# 2021_PWR_REVD.net
KiCad netlist of a schematic drawn in EAGLE
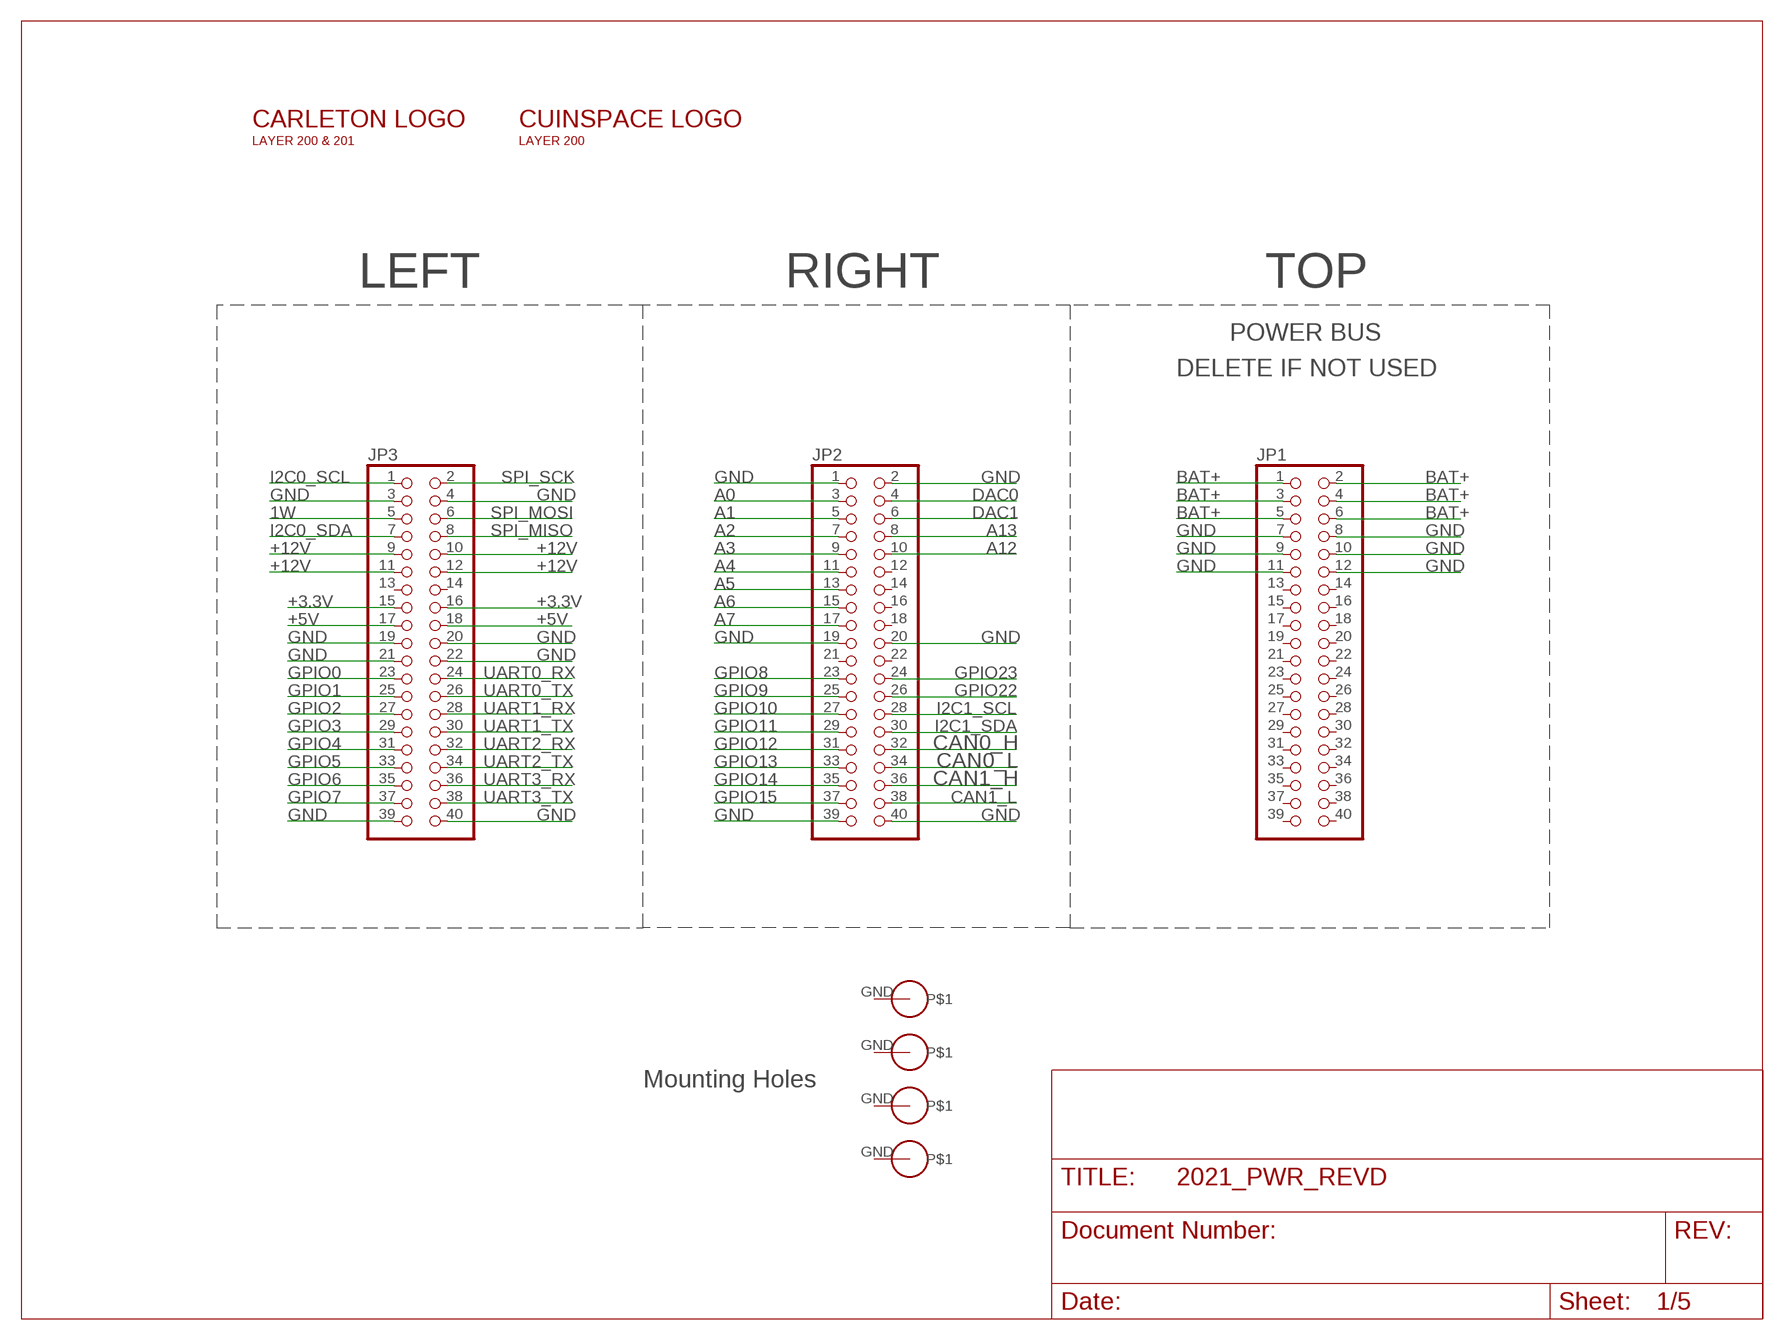
[diagram p0: schematic, sheet 1]
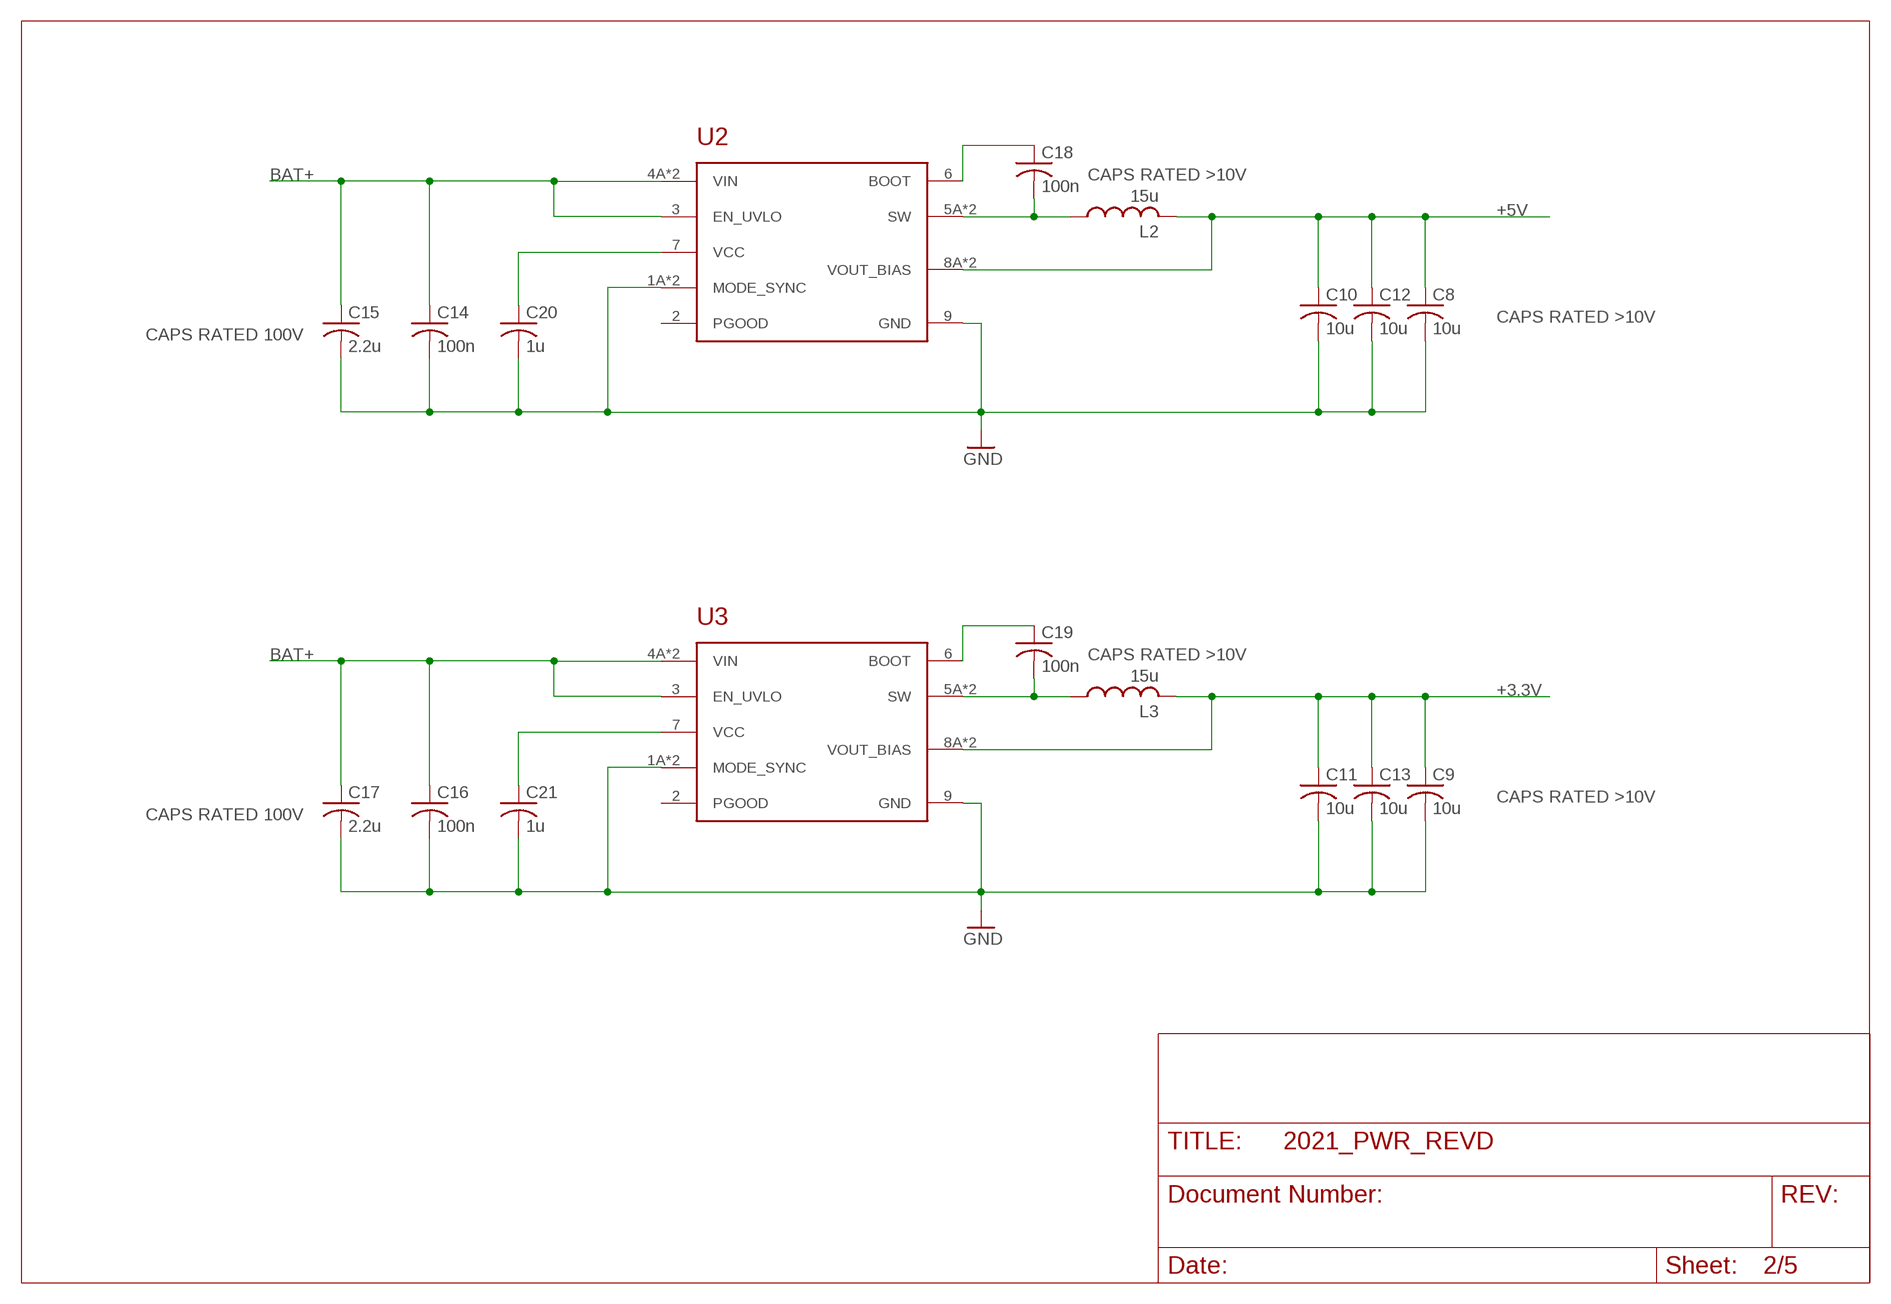
[diagram p1: schematic, sheet 2]
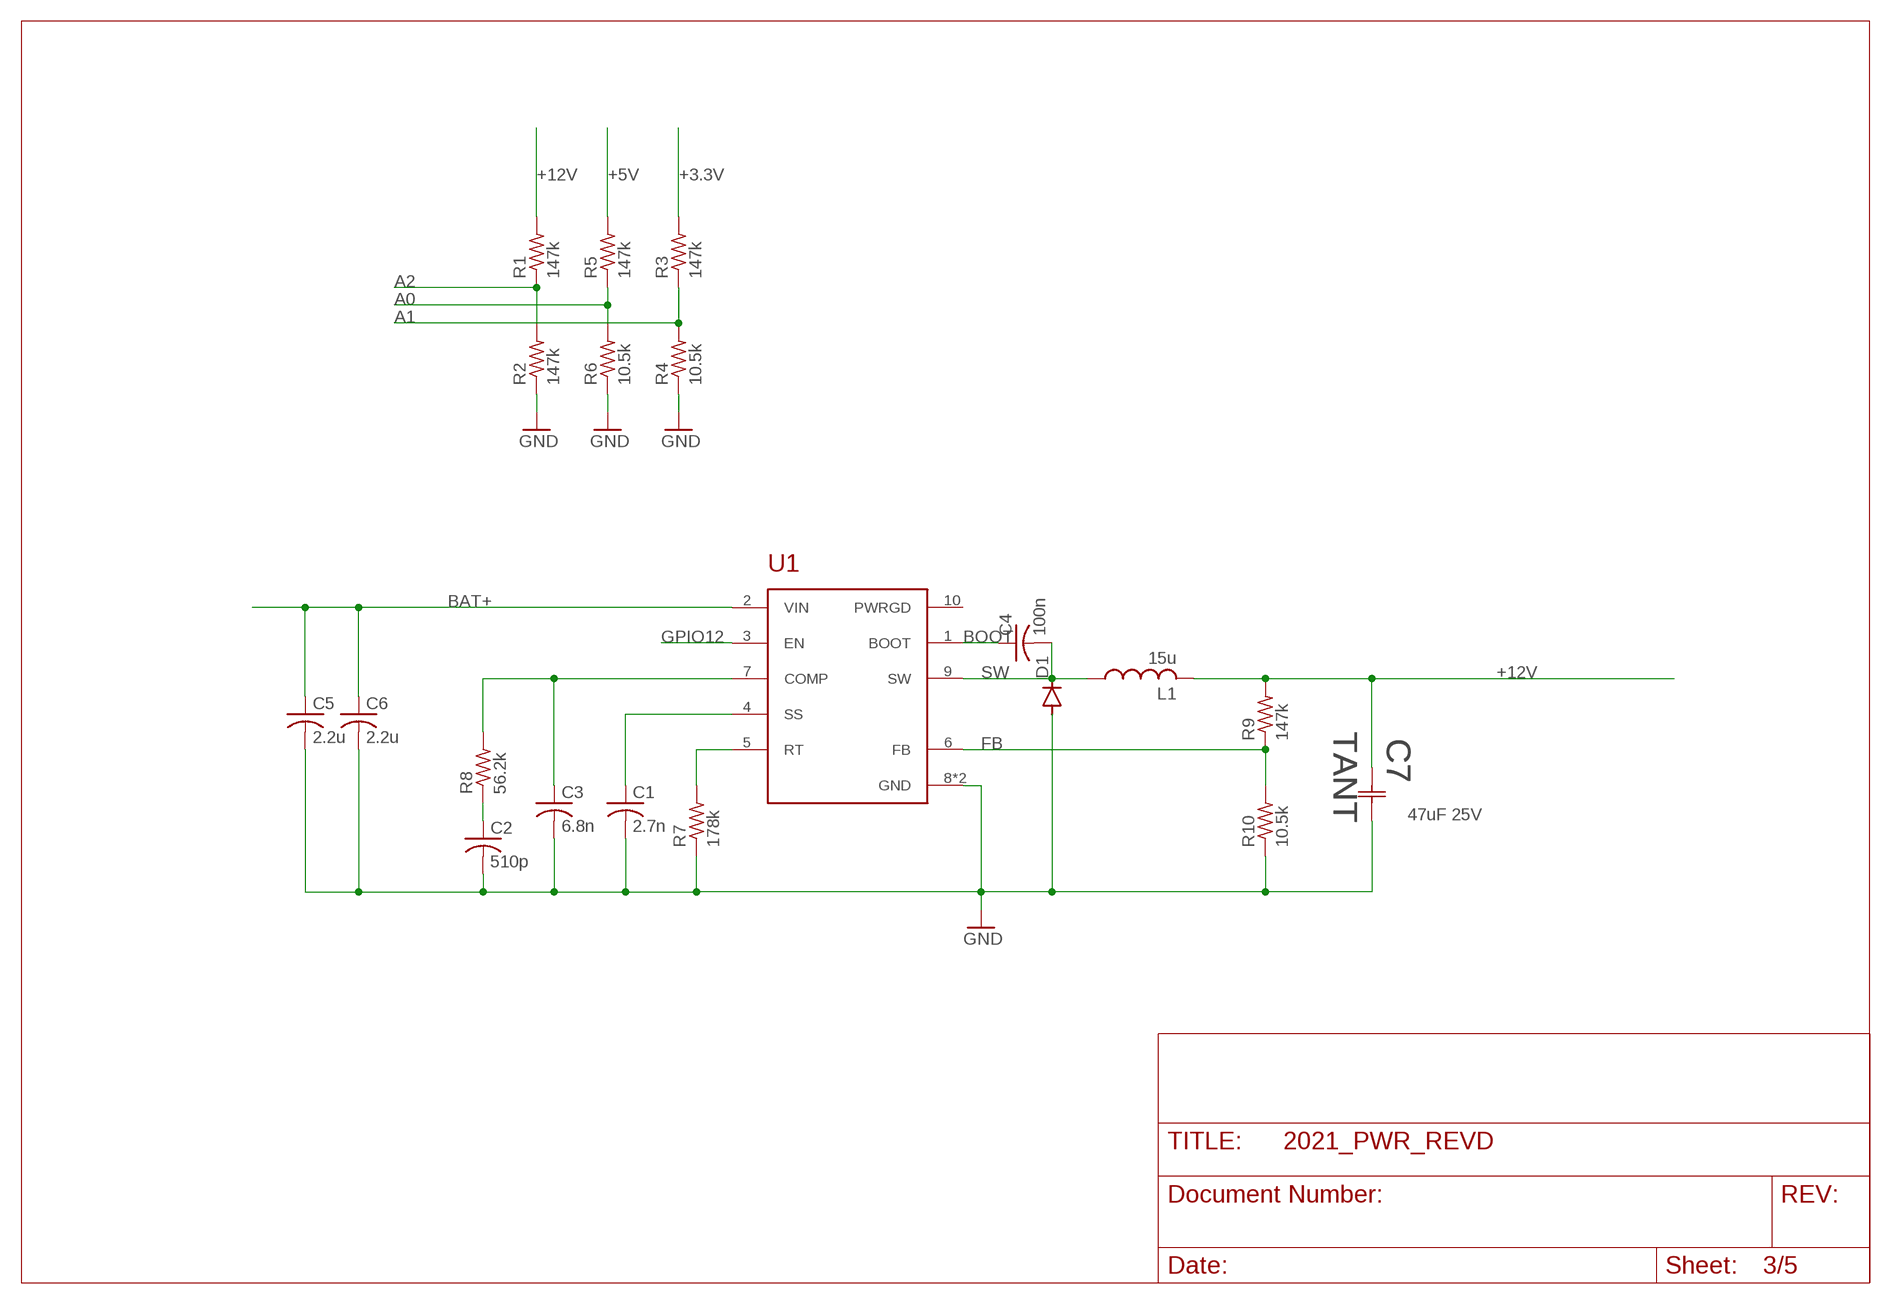
[diagram p2: schematic, sheet 3]

(export (version "E")
  (design (tool "Eeschema 10.0.6"))
  (components
    (comp (ref "C1")
      (value "2.7n")
      (footprint "eagle-import:C0805")
      (libsource (lib "eagle-import") (part "C-USC0805"))
    )
    (comp (ref "C2")
      (value "510p")
      (footprint "eagle-import:C0805")
      (libsource (lib "eagle-import") (part "C-USC0805"))
    )
    (comp (ref "C3")
      (value "6.8n")
      (footprint "eagle-import:C0805")
      (libsource (lib "eagle-import") (part "C-USC0805"))
    )
    (comp (ref "C4")
      (value "100n")
      (footprint "eagle-import:C0805")
      (libsource (lib "eagle-import") (part "C-USC0805"))
    )
    (comp (ref "C5")
      (value "2.2u")
      (footprint "eagle-import:C0805")
      (libsource (lib "eagle-import") (part "C-USC0805"))
    )
    (comp (ref "C6")
      (value "2.2u")
      (footprint "eagle-import:C0805")
      (libsource (lib "eagle-import") (part "C-USC0805"))
    )
    (comp (ref "C7")
      (value "TANT")
      (footprint "eagle-import:TAJD")
      (fields (field (name "MANUFACTURER_PART_NUMBER") "TAJD226K016RNJ"))
      (libsource (lib "eagle-import") (part "TANT"))
    )
    (comp (ref "D1")
      (value "SCH_DIODE_10A_100VFSV10100V")
      (footprint "eagle-import:TO-277-3")
      (libsource (lib "eagle-import") (part "SCH_DIODE_10A_100VFSV10100V"))
    )
    (comp (ref "L1")
      (value "15u")
      (footprint "eagle-import:13.5X12.5")
      (libsource (lib "eagle-import") (part "IND_15UH_9A_28MOHMSRP1265A-150M"))
    )
    (comp (ref "R1")
      (value "147k")
      (footprint "eagle-import:R0805")
      (libsource (lib "eagle-import") (part "R-US_R0805"))
    )
    (comp (ref "R2")
      (value "147k")
      (footprint "eagle-import:R0805")
      (libsource (lib "eagle-import") (part "R-US_R0805"))
    )
    (comp (ref "R3")
      (value "147k")
      (footprint "eagle-import:R0805")
      (libsource (lib "eagle-import") (part "R-US_R0805"))
    )
    (comp (ref "R4")
      (value "10.5k")
      (footprint "eagle-import:R0805")
      (libsource (lib "eagle-import") (part "R-US_R0805"))
    )
    (comp (ref "R5")
      (value "147k")
      (footprint "eagle-import:R0805")
      (libsource (lib "eagle-import") (part "R-US_R0805"))
    )
    (comp (ref "R6")
      (value "10.5k")
      (footprint "eagle-import:R0805")
      (libsource (lib "eagle-import") (part "R-US_R0805"))
    )
    (comp (ref "R7")
      (value "178k")
      (footprint "eagle-import:R0805")
      (libsource (lib "eagle-import") (part "R-US_R0805"))
    )
    (comp (ref "R8")
      (value "56.2k")
      (footprint "eagle-import:R0805")
      (libsource (lib "eagle-import") (part "R-US_R0805"))
    )
    (comp (ref "R9")
      (value "147k")
      (footprint "eagle-import:R0805")
      (libsource (lib "eagle-import") (part "R-US_R0805"))
    )
    (comp (ref "R10")
      (value "10.5k")
      (footprint "eagle-import:R0805")
      (libsource (lib "eagle-import") (part "R-US_R0805"))
    )
    (comp (ref "U1")
      (value "TPS54561")
      (footprint "eagle-import:10-WSON")
      (libsource (lib "eagle-import") (part "TPS54561"))
    )
    (comp (ref "$$U$1")
      (value "PS/104-MOUNTING-HOLE")
      (footprint "eagle-import:PC_104-MOUNTING-HOLE")
      (libsource (lib "eagle-import") (part "PS/104-MOUNTING-HOLE"))
    )
    (comp (ref "JP1")
      (value "PINHD-2X20")
      (footprint "eagle-import:2X20")
      (libsource (lib "eagle-import") (part "PINHD-2X20"))
    )
    (comp (ref "JP2")
      (value "PINHD-2X20")
      (footprint "eagle-import:2X20")
      (libsource (lib "eagle-import") (part "PINHD-2X20"))
    )
    (comp (ref "JP3")
      (value "PINHD-2X20")
      (footprint "eagle-import:2X20")
      (libsource (lib "eagle-import") (part "PINHD-2X20"))
    )
    (comp (ref "U$1")
      (value "PS/104-MOUNTING-HOLE")
      (footprint "eagle-import:PC_104-MOUNTING-HOLE")
      (libsource (lib "eagle-import") (part "PS/104-MOUNTING-HOLE"))
    )
    (comp (ref "U$2")
      (value "PS/104-MOUNTING-HOLE")
      (footprint "eagle-import:PC_104-MOUNTING-HOLE")
      (libsource (lib "eagle-import") (part "PS/104-MOUNTING-HOLE"))
    )
    (comp (ref "U$3")
      (value "PS/104-MOUNTING-HOLE")
      (footprint "eagle-import:PC_104-MOUNTING-HOLE")
      (libsource (lib "eagle-import") (part "PS/104-MOUNTING-HOLE"))
    )
    (comp (ref "U$100")
      (value "INSPACE3CM_L")
      (footprint "eagle-import:INSPACE_3CM_LETTERS")
      (libsource (lib "eagle-import") (part "INSPACE3CM_L"))
    )
    (comp (ref "U$101")
      (value "CARLETON3CM")
      (footprint "eagle-import:CARLETONU_3CM")
      (libsource (lib "eagle-import") (part "CARLETON3CM"))
    )
    (comp (ref "C8")
      (value "10u")
      (footprint "eagle-import:C0805")
      (libsource (lib "eagle-import") (part "C-USC0805"))
    )
    (comp (ref "C9")
      (value "10u")
      (footprint "eagle-import:C0805")
      (libsource (lib "eagle-import") (part "C-USC0805"))
    )
    (comp (ref "C10")
      (value "10u")
      (footprint "eagle-import:C0805")
      (libsource (lib "eagle-import") (part "C-USC0805"))
    )
    (comp (ref "C11")
      (value "10u")
      (footprint "eagle-import:C0805")
      (libsource (lib "eagle-import") (part "C-USC0805"))
    )
    (comp (ref "C12")
      (value "10u")
      (footprint "eagle-import:C0805")
      (libsource (lib "eagle-import") (part "C-USC0805"))
    )
    (comp (ref "C13")
      (value "10u")
      (footprint "eagle-import:C0805")
      (libsource (lib "eagle-import") (part "C-USC0805"))
    )
    (comp (ref "C14")
      (value "100n")
      (footprint "eagle-import:C0805")
      (libsource (lib "eagle-import") (part "C-USC0805"))
    )
    (comp (ref "C15")
      (value "2.2u")
      (footprint "eagle-import:C0805")
      (libsource (lib "eagle-import") (part "C-USC0805"))
    )
    (comp (ref "C16")
      (value "100n")
      (footprint "eagle-import:C0805")
      (libsource (lib "eagle-import") (part "C-USC0805"))
    )
    (comp (ref "C17")
      (value "2.2u")
      (footprint "eagle-import:C0805")
      (libsource (lib "eagle-import") (part "C-USC0805"))
    )
    (comp (ref "C18")
      (value "100n")
      (footprint "eagle-import:C0805")
      (libsource (lib "eagle-import") (part "C-USC0805"))
    )
    (comp (ref "C19")
      (value "100n")
      (footprint "eagle-import:C0805")
      (libsource (lib "eagle-import") (part "C-USC0805"))
    )
    (comp (ref "C20")
      (value "1u")
      (footprint "eagle-import:C0805")
      (libsource (lib "eagle-import") (part "C-USC0805"))
    )
    (comp (ref "C21")
      (value "1u")
      (footprint "eagle-import:C0805")
      (libsource (lib "eagle-import") (part "C-USC0805"))
    )
    (comp (ref "L2")
      (value "15u")
      (footprint "eagle-import:13.5X12.5")
      (libsource (lib "eagle-import") (part "IND_15UH_9A_28MOHMSRP1265A-150M"))
    )
    (comp (ref "L3")
      (value "15u")
      (footprint "eagle-import:13.5X12.5")
      (libsource (lib "eagle-import") (part "IND_15UH_9A_28MOHMSRP1265A-150M"))
    )
    (comp (ref "U2")
      (value "LMR36506LMR36506MSC3")
      (footprint "eagle-import:9-VFQFN")
      (libsource (lib "eagle-import") (part "LMR36506LMR36506MSC3"))
    )
    (comp (ref "U3")
      (value "LMR36506LMR36506MSC3")
      (footprint "eagle-import:9-VFQFN")
      (libsource (lib "eagle-import") (part "LMR36506LMR36506MSC3"))
    )
  )
  (nets
    (net (code "1") (name "+3.3V") (class "Default")
      (node (ref "C11") (pin "1") (pinfunction "1_1") (pintype "passive"))
      (node (ref "C13") (pin "1") (pinfunction "1_1") (pintype "passive"))
      (node (ref "C9") (pin "1") (pinfunction "1_1") (pintype "passive"))
      (node (ref "JP3") (pin "15") (pinfunction "15_15") (pintype "passive"))
      (node (ref "JP3") (pin "16") (pinfunction "16_16") (pintype "passive"))
      (node (ref "L3") (pin "P$2") (pinfunction "2_P$2") (pintype "passive"))
      (node (ref "R3") (pin "2") (pinfunction "2_2") (pintype "passive"))
      (node (ref "U3") (pin "8A") (pinfunction "VOUT_BIAS_8A") (pintype "bidirectional"))
      (node (ref "U3") (pin "8B") (pinfunction "VOUT_BIAS_8B") (pintype "bidirectional"))
    )
    (net (code "2") (name "+5V") (class "Default")
      (node (ref "C10") (pin "1") (pinfunction "1_1") (pintype "passive"))
      (node (ref "C12") (pin "1") (pinfunction "1_1") (pintype "passive"))
      (node (ref "C8") (pin "1") (pinfunction "1_1") (pintype "passive"))
      (node (ref "JP3") (pin "17") (pinfunction "17_17") (pintype "passive"))
      (node (ref "JP3") (pin "18") (pinfunction "18_18") (pintype "passive"))
      (node (ref "L2") (pin "P$2") (pinfunction "2_P$2") (pintype "passive"))
      (node (ref "R5") (pin "2") (pinfunction "2_2") (pintype "passive"))
      (node (ref "U2") (pin "8A") (pinfunction "VOUT_BIAS_8A") (pintype "bidirectional"))
      (node (ref "U2") (pin "8B") (pinfunction "VOUT_BIAS_8B") (pintype "bidirectional"))
    )
    (net (code "3") (name "+12V") (class "Default")
      (node (ref "C7") (pin "1") (pinfunction "11_1") (pintype "passive"))
      (node (ref "JP3") (pin "10") (pinfunction "10_10") (pintype "passive"))
      (node (ref "JP3") (pin "11") (pinfunction "11_11") (pintype "passive"))
      (node (ref "JP3") (pin "12") (pinfunction "12_12") (pintype "passive"))
      (node (ref "JP3") (pin "9") (pinfunction "9_9") (pintype "passive"))
      (node (ref "L1") (pin "P$2") (pinfunction "2_P$2") (pintype "passive"))
      (node (ref "R1") (pin "2") (pinfunction "2_2") (pintype "passive"))
      (node (ref "R9") (pin "2") (pinfunction "2_2") (pintype "passive"))
    )
    (net (code "4") (name "1W") (class "Default")
      (node (ref "JP3") (pin "5") (pinfunction "5_5") (pintype "passive"))
    )
    (net (code "5") (name "A0") (class "Default")
      (node (ref "JP2") (pin "3") (pinfunction "3_3") (pintype "passive"))
      (node (ref "R5") (pin "1") (pinfunction "1_1") (pintype "passive"))
      (node (ref "R6") (pin "2") (pinfunction "2_2") (pintype "passive"))
    )
    (net (code "6") (name "A1") (class "Default")
      (node (ref "JP2") (pin "5") (pinfunction "5_5") (pintype "passive"))
      (node (ref "R3") (pin "1") (pinfunction "1_1") (pintype "passive"))
      (node (ref "R4") (pin "2") (pinfunction "2_2") (pintype "passive"))
    )
    (net (code "7") (name "A2") (class "Default")
      (node (ref "JP2") (pin "7") (pinfunction "7_7") (pintype "passive"))
      (node (ref "R1") (pin "1") (pinfunction "1_1") (pintype "passive"))
      (node (ref "R2") (pin "2") (pinfunction "2_2") (pintype "passive"))
    )
    (net (code "8") (name "A3") (class "Default")
      (node (ref "JP2") (pin "9") (pinfunction "9_9") (pintype "passive"))
    )
    (net (code "9") (name "A4") (class "Default")
      (node (ref "JP2") (pin "11") (pinfunction "11_11") (pintype "passive"))
    )
    (net (code "10") (name "A5") (class "Default")
      (node (ref "JP2") (pin "13") (pinfunction "13_13") (pintype "passive"))
    )
    (net (code "11") (name "A6") (class "Default")
      (node (ref "JP2") (pin "15") (pinfunction "15_15") (pintype "passive"))
    )
    (net (code "12") (name "A7") (class "Default")
      (node (ref "JP2") (pin "17") (pinfunction "17_17") (pintype "passive"))
    )
    (net (code "13") (name "A12") (class "Default")
      (node (ref "JP2") (pin "10") (pinfunction "10_10") (pintype "passive"))
    )
    (net (code "14") (name "A13") (class "Default")
      (node (ref "JP2") (pin "8") (pinfunction "8_8") (pintype "passive"))
    )
    (net (code "15") (name "BAT+") (class "Default")
      (node (ref "C14") (pin "1") (pinfunction "1_1") (pintype "passive"))
      (node (ref "C15") (pin "1") (pinfunction "1_1") (pintype "passive"))
      (node (ref "C16") (pin "1") (pinfunction "1_1") (pintype "passive"))
      (node (ref "C17") (pin "1") (pinfunction "1_1") (pintype "passive"))
      (node (ref "C5") (pin "1") (pinfunction "1_1") (pintype "passive"))
      (node (ref "C6") (pin "1") (pinfunction "1_1") (pintype "passive"))
      (node (ref "JP1") (pin "1") (pinfunction "1_1") (pintype "passive"))
      (node (ref "JP1") (pin "2") (pinfunction "2_2") (pintype "passive"))
      (node (ref "JP1") (pin "3") (pinfunction "3_3") (pintype "passive"))
      (node (ref "JP1") (pin "4") (pinfunction "4_4") (pintype "passive"))
      (node (ref "JP1") (pin "5") (pinfunction "5_5") (pintype "passive"))
      (node (ref "JP1") (pin "6") (pinfunction "6_6") (pintype "passive"))
      (node (ref "U1") (pin "2") (pinfunction "VIN_2") (pintype "bidirectional"))
      (node (ref "U2") (pin "3") (pinfunction "EN_UVLO_3") (pintype "bidirectional"))
      (node (ref "U2") (pin "4A") (pinfunction "VIN_4A") (pintype "bidirectional"))
      (node (ref "U2") (pin "4B") (pinfunction "VIN_4B") (pintype "bidirectional"))
      (node (ref "U3") (pin "3") (pinfunction "EN_UVLO_3") (pintype "bidirectional"))
      (node (ref "U3") (pin "4A") (pinfunction "VIN_4A") (pintype "bidirectional"))
      (node (ref "U3") (pin "4B") (pinfunction "VIN_4B") (pintype "bidirectional"))
    )
    (net (code "16") (name "BOOT") (class "Default")
      (node (ref "C4") (pin "1") (pinfunction "1_1") (pintype "passive"))
      (node (ref "U1") (pin "1") (pinfunction "BOOT_1") (pintype "bidirectional"))
    )
    (net (code "17") (name "CAN0_H") (class "Default")
      (node (ref "JP2") (pin "32") (pinfunction "32_32") (pintype "passive"))
    )
    (net (code "18") (name "CAN0_L") (class "Default")
      (node (ref "JP2") (pin "34") (pinfunction "34_34") (pintype "passive"))
    )
    (net (code "19") (name "CAN1_H") (class "Default")
      (node (ref "JP2") (pin "36") (pinfunction "36_36") (pintype "passive"))
    )
    (net (code "20") (name "CAN1_L") (class "Default")
      (node (ref "JP2") (pin "38") (pinfunction "38_38") (pintype "passive"))
    )
    (net (code "21") (name "DAC0") (class "Default")
      (node (ref "JP2") (pin "4") (pinfunction "4_4") (pintype "passive"))
    )
    (net (code "22") (name "DAC1") (class "Default")
      (node (ref "JP2") (pin "6") (pinfunction "6_6") (pintype "passive"))
    )
    (net (code "23") (name "FB") (class "Default")
      (node (ref "R10") (pin "2") (pinfunction "2_2") (pintype "passive"))
      (node (ref "R9") (pin "1") (pinfunction "1_1") (pintype "passive"))
      (node (ref "U1") (pin "6") (pinfunction "FB_6") (pintype "bidirectional"))
    )
    (net (code "24") (name "GND") (class "Default")
      (node (ref "C1") (pin "2") (pinfunction "2_2") (pintype "passive"))
      (node (ref "C10") (pin "2") (pinfunction "2_2") (pintype "passive"))
      (node (ref "C11") (pin "2") (pinfunction "2_2") (pintype "passive"))
      (node (ref "C12") (pin "2") (pinfunction "2_2") (pintype "passive"))
      (node (ref "C13") (pin "2") (pinfunction "2_2") (pintype "passive"))
      (node (ref "C14") (pin "2") (pinfunction "2_2") (pintype "passive"))
      (node (ref "C15") (pin "2") (pinfunction "2_2") (pintype "passive"))
      (node (ref "C16") (pin "2") (pinfunction "2_2") (pintype "passive"))
      (node (ref "C17") (pin "2") (pinfunction "2_2") (pintype "passive"))
      (node (ref "C2") (pin "2") (pinfunction "2_2") (pintype "passive"))
      (node (ref "C20") (pin "2") (pinfunction "2_2") (pintype "passive"))
      (node (ref "C21") (pin "2") (pinfunction "2_2") (pintype "passive"))
      (node (ref "C3") (pin "2") (pinfunction "2_2") (pintype "passive"))
      (node (ref "C5") (pin "2") (pinfunction "2_2") (pintype "passive"))
      (node (ref "C6") (pin "2") (pinfunction "2_2") (pintype "passive"))
      (node (ref "C7") (pin "2") (pinfunction "22_2") (pintype "passive"))
      (node (ref "C8") (pin "2") (pinfunction "2_2") (pintype "passive"))
      (node (ref "C9") (pin "2") (pinfunction "2_2") (pintype "passive"))
      (node (ref "D1") (pin "P$2") (pinfunction "A_P$2") (pintype "passive"))
      (node (ref "D1") (pin "P$3") (pinfunction "A_P$3") (pintype "passive"))
      (node (ref "JP1") (pin "10") (pinfunction "10_10") (pintype "passive"))
      (node (ref "JP1") (pin "11") (pinfunction "11_11") (pintype "passive"))
      (node (ref "JP1") (pin "12") (pinfunction "12_12") (pintype "passive"))
      (node (ref "JP1") (pin "7") (pinfunction "7_7") (pintype "passive"))
      (node (ref "JP1") (pin "8") (pinfunction "8_8") (pintype "passive"))
      (node (ref "JP1") (pin "9") (pinfunction "9_9") (pintype "passive"))
      (node (ref "JP2") (pin "1") (pinfunction "1_1") (pintype "passive"))
      (node (ref "JP2") (pin "19") (pinfunction "19_19") (pintype "passive"))
      (node (ref "JP2") (pin "2") (pinfunction "2_2") (pintype "passive"))
      (node (ref "JP2") (pin "20") (pinfunction "20_20") (pintype "passive"))
      (node (ref "JP2") (pin "39") (pinfunction "39_39") (pintype "passive"))
      (node (ref "JP2") (pin "40") (pinfunction "40_40") (pintype "passive"))
      (node (ref "JP3") (pin "19") (pinfunction "19_19") (pintype "passive"))
      (node (ref "JP3") (pin "20") (pinfunction "20_20") (pintype "passive"))
      (node (ref "JP3") (pin "21") (pinfunction "21_21") (pintype "passive"))
      (node (ref "JP3") (pin "22") (pinfunction "22_22") (pintype "passive"))
      (node (ref "JP3") (pin "3") (pinfunction "3_3") (pintype "passive"))
      (node (ref "JP3") (pin "39") (pinfunction "39_39") (pintype "passive"))
      (node (ref "JP3") (pin "4") (pinfunction "4_4") (pintype "passive"))
      (node (ref "JP3") (pin "40") (pinfunction "40_40") (pintype "passive"))
      (node (ref "R10") (pin "1") (pinfunction "1_1") (pintype "passive"))
      (node (ref "R2") (pin "1") (pinfunction "1_1") (pintype "passive"))
      (node (ref "R4") (pin "1") (pinfunction "1_1") (pintype "passive"))
      (node (ref "R6") (pin "1") (pinfunction "1_1") (pintype "passive"))
      (node (ref "R7") (pin "1") (pinfunction "1_1") (pintype "passive"))
      (node (ref "U1") (pin "11") (pinfunction "GND_11") (pintype "bidirectional"))
      (node (ref "U1") (pin "8") (pinfunction "GND_8") (pintype "bidirectional"))
      (node (ref "U2") (pin "1A") (pinfunction "MODE_SYNC_1A") (pintype "bidirectional"))
      (node (ref "U2") (pin "1B") (pinfunction "MODE_SYNC_1B") (pintype "bidirectional"))
      (node (ref "U2") (pin "9") (pinfunction "GND_9") (pintype "bidirectional"))
      (node (ref "U3") (pin "1A") (pinfunction "MODE_SYNC_1A") (pintype "bidirectional"))
      (node (ref "U3") (pin "1B") (pinfunction "MODE_SYNC_1B") (pintype "bidirectional"))
      (node (ref "U3") (pin "9") (pinfunction "GND_9") (pintype "bidirectional"))
    )
    (net (code "25") (name "GPIO0") (class "Default")
      (node (ref "JP3") (pin "23") (pinfunction "23_23") (pintype "passive"))
    )
    (net (code "26") (name "GPIO1") (class "Default")
      (node (ref "JP3") (pin "25") (pinfunction "25_25") (pintype "passive"))
    )
    (net (code "27") (name "GPIO2") (class "Default")
      (node (ref "JP3") (pin "27") (pinfunction "27_27") (pintype "passive"))
    )
    (net (code "28") (name "GPIO3") (class "Default")
      (node (ref "JP3") (pin "29") (pinfunction "29_29") (pintype "passive"))
    )
    (net (code "29") (name "GPIO4") (class "Default")
      (node (ref "JP3") (pin "31") (pinfunction "31_31") (pintype "passive"))
    )
    (net (code "30") (name "GPIO5") (class "Default")
      (node (ref "JP3") (pin "33") (pinfunction "33_33") (pintype "passive"))
    )
    (net (code "31") (name "GPIO6") (class "Default")
      (node (ref "JP3") (pin "35") (pinfunction "35_35") (pintype "passive"))
    )
    (net (code "32") (name "GPIO7") (class "Default")
      (node (ref "JP3") (pin "37") (pinfunction "37_37") (pintype "passive"))
    )
    (net (code "33") (name "GPIO8") (class "Default")
      (node (ref "JP2") (pin "23") (pinfunction "23_23") (pintype "passive"))
    )
    (net (code "34") (name "GPIO9") (class "Default")
      (node (ref "JP2") (pin "25") (pinfunction "25_25") (pintype "passive"))
    )
    (net (code "35") (name "GPIO10") (class "Default")
      (node (ref "JP2") (pin "27") (pinfunction "27_27") (pintype "passive"))
    )
    (net (code "36") (name "GPIO11") (class "Default")
      (node (ref "JP2") (pin "29") (pinfunction "29_29") (pintype "passive"))
    )
    (net (code "37") (name "GPIO12") (class "Default")
      (node (ref "JP2") (pin "31") (pinfunction "31_31") (pintype "passive"))
      (node (ref "U1") (pin "3") (pinfunction "EN_3") (pintype "bidirectional"))
    )
    (net (code "38") (name "GPIO13") (class "Default")
      (node (ref "JP2") (pin "33") (pinfunction "33_33") (pintype "passive"))
    )
    (net (code "39") (name "GPIO14") (class "Default")
      (node (ref "JP2") (pin "35") (pinfunction "35_35") (pintype "passive"))
    )
    (net (code "40") (name "GPIO15") (class "Default")
      (node (ref "JP2") (pin "37") (pinfunction "37_37") (pintype "passive"))
    )
    (net (code "41") (name "GPIO22") (class "Default")
      (node (ref "JP2") (pin "26") (pinfunction "26_26") (pintype "passive"))
    )
    (net (code "42") (name "GPIO23") (class "Default")
      (node (ref "JP2") (pin "24") (pinfunction "24_24") (pintype "passive"))
    )
    (net (code "43") (name "I2C0_SCL") (class "Default")
      (node (ref "JP3") (pin "1") (pinfunction "1_1") (pintype "passive"))
    )
    (net (code "44") (name "I2C0_SDA") (class "Default")
      (node (ref "JP3") (pin "7") (pinfunction "7_7") (pintype "passive"))
    )
    (net (code "45") (name "I2C1_SCL") (class "Default")
      (node (ref "JP2") (pin "28") (pinfunction "28_28") (pintype "passive"))
    )
    (net (code "46") (name "I2C1_SDA") (class "Default")
      (node (ref "JP2") (pin "30") (pinfunction "30_30") (pintype "passive"))
    )
    (net (code "47") (name "Net-(C2-Pad1)") (class "Default")
      (node (ref "C2") (pin "1") (pinfunction "1_1") (pintype "passive"))
      (node (ref "R8") (pin "1") (pinfunction "1_1") (pintype "passive"))
    )
    (net (code "48") (name "Net-(L2-1)") (class "Default")
      (node (ref "C18") (pin "2") (pinfunction "2_2") (pintype "passive"))
      (node (ref "L2") (pin "P$1") (pinfunction "1_P$1") (pintype "passive"))
      (node (ref "U2") (pin "5A") (pinfunction "SW_5A") (pintype "bidirectional"))
      (node (ref "U2") (pin "5B") (pinfunction "SW_5B") (pintype "bidirectional"))
    )
    (net (code "49") (name "Net-(L3-1)") (class "Default")
      (node (ref "C19") (pin "2") (pinfunction "2_2") (pintype "passive"))
      (node (ref "L3") (pin "P$1") (pinfunction "1_P$1") (pintype "passive"))
      (node (ref "U3") (pin "5A") (pinfunction "SW_5A") (pintype "bidirectional"))
      (node (ref "U3") (pin "5B") (pinfunction "SW_5B") (pintype "bidirectional"))
    )
    (net (code "50") (name "Net-(U1-COMP)") (class "Default")
      (node (ref "C3") (pin "1") (pinfunction "1_1") (pintype "passive"))
      (node (ref "R8") (pin "2") (pinfunction "2_2") (pintype "passive"))
      (node (ref "U1") (pin "7") (pinfunction "COMP_7") (pintype "bidirectional"))
    )
    (net (code "51") (name "Net-(U1-RT)") (class "Default")
      (node (ref "R7") (pin "2") (pinfunction "2_2") (pintype "passive"))
      (node (ref "U1") (pin "5") (pinfunction "RT_5") (pintype "bidirectional"))
    )
    (net (code "52") (name "Net-(U1-SS)") (class "Default")
      (node (ref "C1") (pin "1") (pinfunction "1_1") (pintype "passive"))
      (node (ref "U1") (pin "4") (pinfunction "SS_4") (pintype "bidirectional"))
    )
    (net (code "53") (name "Net-(U2-BOOT)") (class "Default")
      (node (ref "C18") (pin "1") (pinfunction "1_1") (pintype "passive"))
      (node (ref "U2") (pin "6") (pinfunction "BOOT_6") (pintype "bidirectional"))
    )
    (net (code "54") (name "Net-(U2-VCC)") (class "Default")
      (node (ref "C20") (pin "1") (pinfunction "1_1") (pintype "passive"))
      (node (ref "U2") (pin "7") (pinfunction "VCC_7") (pintype "bidirectional"))
    )
    (net (code "55") (name "Net-(U3-BOOT)") (class "Default")
      (node (ref "C19") (pin "1") (pinfunction "1_1") (pintype "passive"))
      (node (ref "U3") (pin "6") (pinfunction "BOOT_6") (pintype "bidirectional"))
    )
    (net (code "56") (name "Net-(U3-VCC)") (class "Default")
      (node (ref "C21") (pin "1") (pinfunction "1_1") (pintype "passive"))
      (node (ref "U3") (pin "7") (pinfunction "VCC_7") (pintype "bidirectional"))
    )
    (net (code "57") (name "SPI_MISO") (class "Default")
      (node (ref "JP3") (pin "8") (pinfunction "8_8") (pintype "passive"))
    )
    (net (code "58") (name "SPI_MOSI") (class "Default")
      (node (ref "JP3") (pin "6") (pinfunction "6_6") (pintype "passive"))
    )
    (net (code "59") (name "SPI_SCK") (class "Default")
      (node (ref "JP3") (pin "2") (pinfunction "2_2") (pintype "passive"))
    )
    (net (code "60") (name "SW") (class "Default")
      (node (ref "C4") (pin "2") (pinfunction "2_2") (pintype "passive"))
      (node (ref "D1") (pin "P$1") (pinfunction "C_P$1") (pintype "passive"))
      (node (ref "L1") (pin "P$1") (pinfunction "1_P$1") (pintype "passive"))
      (node (ref "U1") (pin "9") (pinfunction "SW_9") (pintype "bidirectional"))
    )
    (net (code "61") (name "UART0_RX") (class "Default")
      (node (ref "JP3") (pin "24") (pinfunction "24_24") (pintype "passive"))
    )
    (net (code "62") (name "UART0_TX") (class "Default")
      (node (ref "JP3") (pin "26") (pinfunction "26_26") (pintype "passive"))
    )
    (net (code "63") (name "UART1_RX") (class "Default")
      (node (ref "JP3") (pin "28") (pinfunction "28_28") (pintype "passive"))
    )
    (net (code "64") (name "UART1_TX") (class "Default")
      (node (ref "JP3") (pin "30") (pinfunction "30_30") (pintype "passive"))
    )
    (net (code "65") (name "UART2_RX") (class "Default")
      (node (ref "JP3") (pin "32") (pinfunction "32_32") (pintype "passive"))
    )
    (net (code "66") (name "UART2_TX") (class "Default")
      (node (ref "JP3") (pin "34") (pinfunction "34_34") (pintype "passive"))
    )
    (net (code "67") (name "UART3_RX") (class "Default")
      (node (ref "JP3") (pin "36") (pinfunction "36_36") (pintype "passive"))
    )
    (net (code "68") (name "UART3_TX") (class "Default")
      (node (ref "JP3") (pin "38") (pinfunction "38_38") (pintype "passive"))
    )
    (net (code "69") (name "unconnected-($$U$1-P$1-PadGND)") (class "Default")
      (node (ref "$$U$1") (pin "GND") (pinfunction "P$1_GND") (pintype "bidirectional"))
    )
    (net (code "70") (name "unconnected-(JP1-Pad13)") (class "Default")
      (node (ref "JP1") (pin "13") (pinfunction "13_13") (pintype "passive"))
    )
    (net (code "71") (name "unconnected-(JP1-Pad14)") (class "Default")
      (node (ref "JP1") (pin "14") (pinfunction "14_14") (pintype "passive"))
    )
    (net (code "72") (name "unconnected-(JP1-Pad15)") (class "Default")
      (node (ref "JP1") (pin "15") (pinfunction "15_15") (pintype "passive"))
    )
    (net (code "73") (name "unconnected-(JP1-Pad16)") (class "Default")
      (node (ref "JP1") (pin "16") (pinfunction "16_16") (pintype "passive"))
    )
    (net (code "74") (name "unconnected-(JP1-Pad17)") (class "Default")
      (node (ref "JP1") (pin "17") (pinfunction "17_17") (pintype "passive"))
    )
    (net (code "75") (name "unconnected-(JP1-Pad18)") (class "Default")
      (node (ref "JP1") (pin "18") (pinfunction "18_18") (pintype "passive"))
    )
    (net (code "76") (name "unconnected-(JP1-Pad19)") (class "Default")
      (node (ref "JP1") (pin "19") (pinfunction "19_19") (pintype "passive"))
    )
    (net (code "77") (name "unconnected-(JP1-Pad20)") (class "Default")
      (node (ref "JP1") (pin "20") (pinfunction "20_20") (pintype "passive"))
    )
    (net (code "78") (name "unconnected-(JP1-Pad21)") (class "Default")
      (node (ref "JP1") (pin "21") (pinfunction "21_21") (pintype "passive"))
    )
    (net (code "79") (name "unconnected-(JP1-Pad22)") (class "Default")
      (node (ref "JP1") (pin "22") (pinfunction "22_22") (pintype "passive"))
    )
    (net (code "80") (name "unconnected-(JP1-Pad23)") (class "Default")
      (node (ref "JP1") (pin "23") (pinfunction "23_23") (pintype "passive"))
    )
    (net (code "81") (name "unconnected-(JP1-Pad24)") (class "Default")
      (node (ref "JP1") (pin "24") (pinfunction "24_24") (pintype "passive"))
    )
    (net (code "82") (name "unconnected-(JP1-Pad25)") (class "Default")
      (node (ref "JP1") (pin "25") (pinfunction "25_25") (pintype "passive"))
    )
    (net (code "83") (name "unconnected-(JP1-Pad26)") (class "Default")
      (node (ref "JP1") (pin "26") (pinfunction "26_26") (pintype "passive"))
    )
    (net (code "84") (name "unconnected-(JP1-Pad27)") (class "Default")
      (node (ref "JP1") (pin "27") (pinfunction "27_27") (pintype "passive"))
    )
    (net (code "85") (name "unconnected-(JP1-Pad28)") (class "Default")
      (node (ref "JP1") (pin "28") (pinfunction "28_28") (pintype "passive"))
    )
    (net (code "86") (name "unconnected-(JP1-Pad29)") (class "Default")
      (node (ref "JP1") (pin "29") (pinfunction "29_29") (pintype "passive"))
    )
    (net (code "87") (name "unconnected-(JP1-Pad30)") (class "Default")
      (node (ref "JP1") (pin "30") (pinfunction "30_30") (pintype "passive"))
    )
    (net (code "88") (name "unconnected-(JP1-Pad31)") (class "Default")
      (node (ref "JP1") (pin "31") (pinfunction "31_31") (pintype "passive"))
    )
    (net (code "89") (name "unconnected-(JP1-Pad32)") (class "Default")
      (node (ref "JP1") (pin "32") (pinfunction "32_32") (pintype "passive"))
    )
    (net (code "90") (name "unconnected-(JP1-Pad33)") (class "Default")
      (node (ref "JP1") (pin "33") (pinfunction "33_33") (pintype "passive"))
    )
    (net (code "91") (name "unconnected-(JP1-Pad34)") (class "Default")
      (node (ref "JP1") (pin "34") (pinfunction "34_34") (pintype "passive"))
    )
    (net (code "92") (name "unconnected-(JP1-Pad35)") (class "Default")
      (node (ref "JP1") (pin "35") (pinfunction "35_35") (pintype "passive"))
    )
    (net (code "93") (name "unconnected-(JP1-Pad36)") (class "Default")
      (node (ref "JP1") (pin "36") (pinfunction "36_36") (pintype "passive"))
    )
    (net (code "94") (name "unconnected-(JP1-Pad37)") (class "Default")
      (node (ref "JP1") (pin "37") (pinfunction "37_37") (pintype "passive"))
    )
    (net (code "95") (name "unconnected-(JP1-Pad38)") (class "Default")
      (node (ref "JP1") (pin "38") (pinfunction "38_38") (pintype "passive"))
    )
    (net (code "96") (name "unconnected-(JP1-Pad39)") (class "Default")
      (node (ref "JP1") (pin "39") (pinfunction "39_39") (pintype "passive"))
    )
    (net (code "97") (name "unconnected-(JP1-Pad40)") (class "Default")
      (node (ref "JP1") (pin "40") (pinfunction "40_40") (pintype "passive"))
    )
    (net (code "98") (name "unconnected-(JP2-Pad12)") (class "Default")
      (node (ref "JP2") (pin "12") (pinfunction "12_12") (pintype "passive"))
    )
    (net (code "99") (name "unconnected-(JP2-Pad14)") (class "Default")
      (node (ref "JP2") (pin "14") (pinfunction "14_14") (pintype "passive"))
    )
    (net (code "100") (name "unconnected-(JP2-Pad16)") (class "Default")
      (node (ref "JP2") (pin "16") (pinfunction "16_16") (pintype "passive"))
    )
    (net (code "101") (name "unconnected-(JP2-Pad18)") (class "Default")
      (node (ref "JP2") (pin "18") (pinfunction "18_18") (pintype "passive"))
    )
    (net (code "102") (name "unconnected-(JP2-Pad21)") (class "Default")
      (node (ref "JP2") (pin "21") (pinfunction "21_21") (pintype "passive"))
    )
    (net (code "103") (name "unconnected-(JP2-Pad22)") (class "Default")
      (node (ref "JP2") (pin "22") (pinfunction "22_22") (pintype "passive"))
    )
    (net (code "104") (name "unconnected-(JP3-Pad13)") (class "Default")
      (node (ref "JP3") (pin "13") (pinfunction "13_13") (pintype "passive"))
    )
    (net (code "105") (name "unconnected-(JP3-Pad14)") (class "Default")
      (node (ref "JP3") (pin "14") (pinfunction "14_14") (pintype "passive"))
    )
    (net (code "106") (name "unconnected-(U$1-P$1-PadGND)") (class "Default")
      (node (ref "U$1") (pin "GND") (pinfunction "P$1_GND") (pintype "bidirectional"))
    )
    (net (code "107") (name "unconnected-(U$2-P$1-PadGND)") (class "Default")
      (node (ref "U$2") (pin "GND") (pinfunction "P$1_GND") (pintype "bidirectional"))
    )
    (net (code "108") (name "unconnected-(U$3-P$1-PadGND)") (class "Default")
      (node (ref "U$3") (pin "GND") (pinfunction "P$1_GND") (pintype "bidirectional"))
    )
    (net (code "109") (name "unconnected-(U1-PWRGD-Pad10)") (class "Default")
      (node (ref "U1") (pin "10") (pinfunction "PWRGD_10") (pintype "bidirectional"))
    )
    (net (code "110") (name "unconnected-(U2-PGOOD-Pad2)") (class "Default")
      (node (ref "U2") (pin "2") (pinfunction "PGOOD_2") (pintype "bidirectional"))
    )
    (net (code "111") (name "unconnected-(U3-PGOOD-Pad2)") (class "Default")
      (node (ref "U3") (pin "2") (pinfunction "PGOOD_2") (pintype "bidirectional"))
    )
  )
)
